# opencmxx.net
KiCad netlist of a schematic drawn in EAGLE
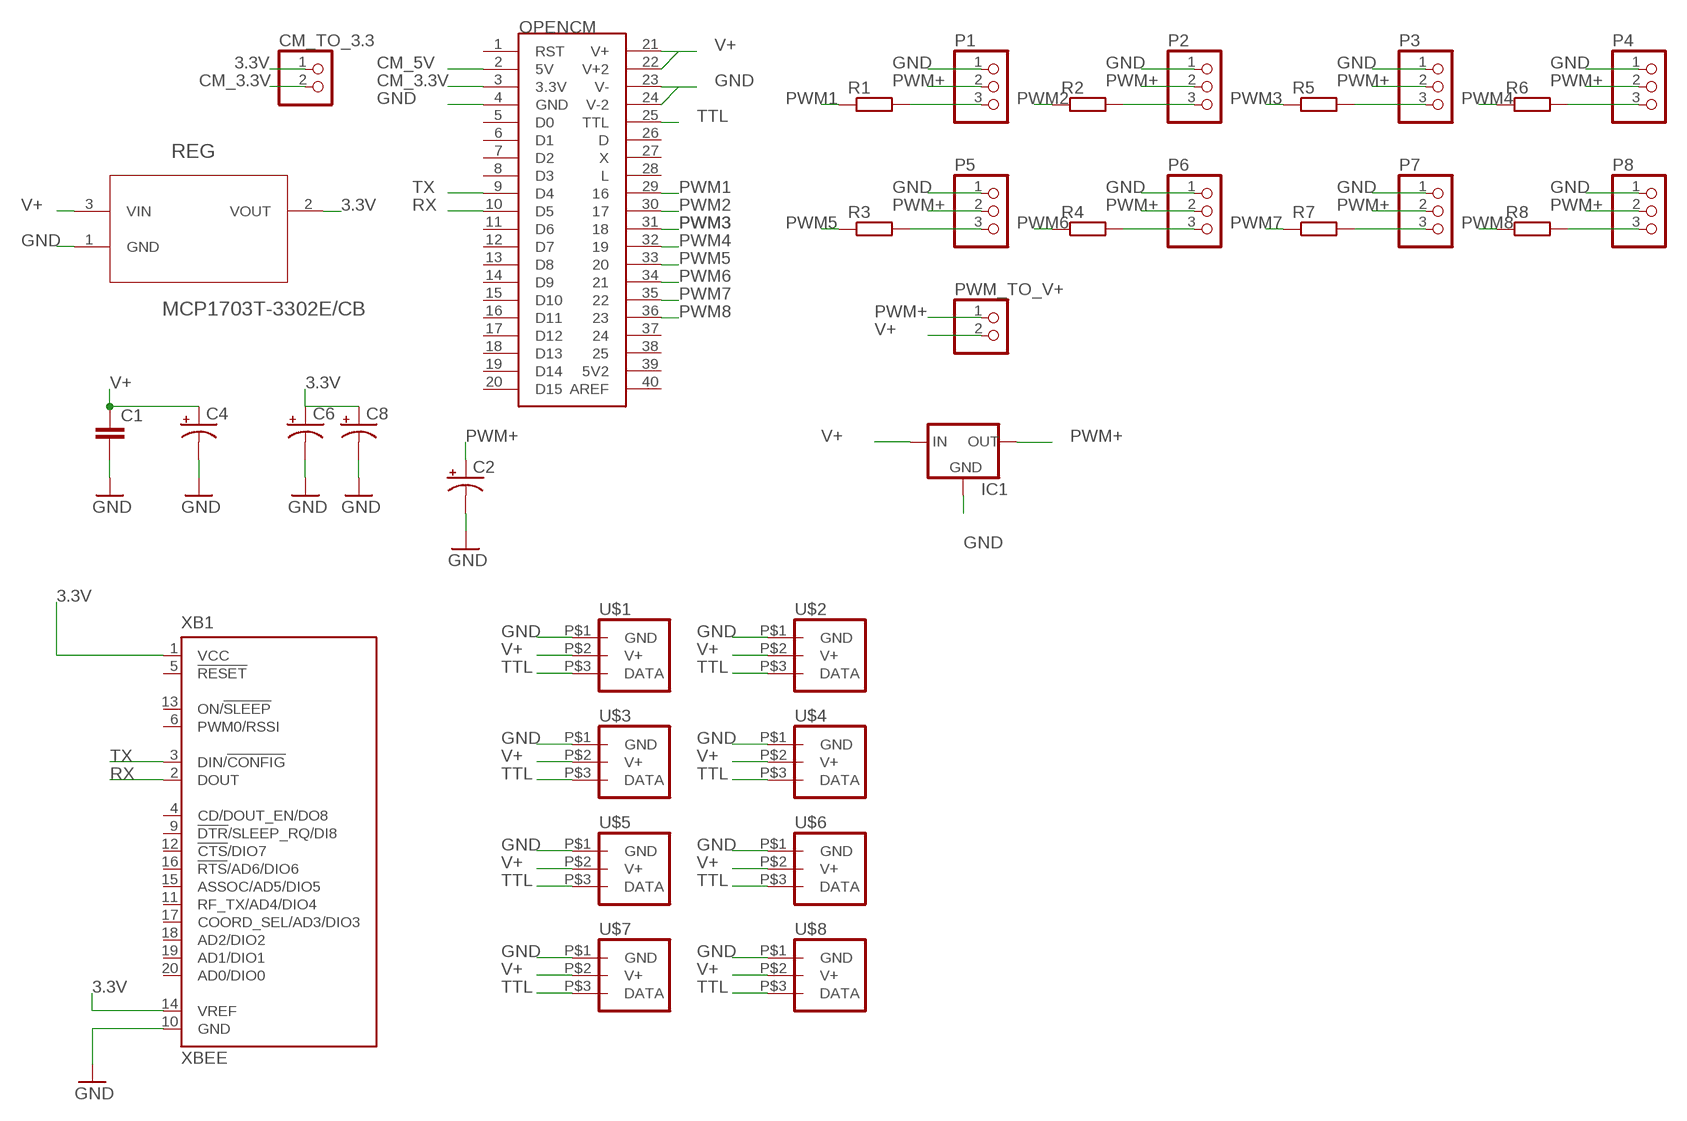
[diagram p0: schematic, sheet 1]

(export (version "E")
  (design (tool "Eeschema 10.0.6"))
  (components
    (comp (ref "C1")
      (value "C-EU075-032X103")
      (footprint "eagle-import:C075-032X103")
      (libsource (lib "eagle-import") (part "C-EU075-032X103"))
    )
    (comp (ref "C2")
      (value "CAP_POLPTH2")
      (footprint "eagle-import:CPOL-RADIAL-10UF-25V")
      (libsource (lib "eagle-import") (part "CAP_POLPTH2"))
    )
    (comp (ref "C4")
      (value "CAP_POLPTH2")
      (footprint "eagle-import:CPOL-RADIAL-10UF-25V")
      (libsource (lib "eagle-import") (part "CAP_POLPTH2"))
    )
    (comp (ref "C6")
      (value "CAP_POLPTH2")
      (footprint "eagle-import:CPOL-RADIAL-10UF-25V")
      (libsource (lib "eagle-import") (part "CAP_POLPTH2"))
    )
    (comp (ref "C8")
      (value "CAP_POLPTH2")
      (footprint "eagle-import:CPOL-RADIAL-10UF-25V")
      (libsource (lib "eagle-import") (part "CAP_POLPTH2"))
    )
    (comp (ref "CM_TO_3.3")
      (value "CONNEC_1X02")
      (footprint "eagle-import:CONNEC_1X02")
      (libsource (lib "eagle-import") (part "CONNEC_1X02"))
    )
    (comp (ref "IC1")
      (value "V_REG_78XXSIDE")
      (footprint "eagle-import:78XXL")
      (libsource (lib "eagle-import") (part "V_REG_78XXSIDE"))
    )
    (comp (ref "OPENCM")
      (value "OPENCM")
      (footprint "eagle-import:OPENCM")
      (libsource (lib "eagle-import") (part "OPENCM"))
    )
    (comp (ref "P1")
      (value "CONNEC_1X03")
      (footprint "eagle-import:CONNEC_1X03")
      (libsource (lib "eagle-import") (part "CONNEC_1X03"))
    )
    (comp (ref "P2")
      (value "CONNEC_1X03")
      (footprint "eagle-import:CONNEC_1X03")
      (libsource (lib "eagle-import") (part "CONNEC_1X03"))
    )
    (comp (ref "P3")
      (value "CONNEC_1X03")
      (footprint "eagle-import:CONNEC_1X03")
      (libsource (lib "eagle-import") (part "CONNEC_1X03"))
    )
    (comp (ref "P4")
      (value "CONNEC_1X03")
      (footprint "eagle-import:CONNEC_1X03")
      (libsource (lib "eagle-import") (part "CONNEC_1X03"))
    )
    (comp (ref "P5")
      (value "CONNEC_1X03")
      (footprint "eagle-import:CONNEC_1X03")
      (libsource (lib "eagle-import") (part "CONNEC_1X03"))
    )
    (comp (ref "P6")
      (value "CONNEC_1X03")
      (footprint "eagle-import:CONNEC_1X03")
      (libsource (lib "eagle-import") (part "CONNEC_1X03"))
    )
    (comp (ref "P7")
      (value "CONNEC_1X03")
      (footprint "eagle-import:CONNEC_1X03")
      (libsource (lib "eagle-import") (part "CONNEC_1X03"))
    )
    (comp (ref "P8")
      (value "CONNEC_1X03")
      (footprint "eagle-import:CONNEC_1X03")
      (libsource (lib "eagle-import") (part "CONNEC_1X03"))
    )
    (comp (ref "PWM_TO_V+")
      (value "CONNEC_1X02")
      (footprint "eagle-import:CONNEC_1X02")
      (libsource (lib "eagle-import") (part "CONNEC_1X02"))
    )
    (comp (ref "R1")
      (value "RESISTANCE-R0805")
      (footprint "eagle-import:R0805")
      (libsource (lib "eagle-import") (part "RESISTANCE-R0805"))
    )
    (comp (ref "R2")
      (value "RESISTANCE-R0805")
      (footprint "eagle-import:R0805")
      (libsource (lib "eagle-import") (part "RESISTANCE-R0805"))
    )
    (comp (ref "R3")
      (value "RESISTANCE-R0805")
      (footprint "eagle-import:R0805")
      (libsource (lib "eagle-import") (part "RESISTANCE-R0805"))
    )
    (comp (ref "R4")
      (value "RESISTANCE-R0805")
      (footprint "eagle-import:R0805")
      (libsource (lib "eagle-import") (part "RESISTANCE-R0805"))
    )
    (comp (ref "R5")
      (value "RESISTANCE-R0805")
      (footprint "eagle-import:R0805")
      (libsource (lib "eagle-import") (part "RESISTANCE-R0805"))
    )
    (comp (ref "R6")
      (value "RESISTANCE-R0805")
      (footprint "eagle-import:R0805")
      (libsource (lib "eagle-import") (part "RESISTANCE-R0805"))
    )
    (comp (ref "R7")
      (value "RESISTANCE-R0805")
      (footprint "eagle-import:R0805")
      (libsource (lib "eagle-import") (part "RESISTANCE-R0805"))
    )
    (comp (ref "R8")
      (value "RESISTANCE-R0805")
      (footprint "eagle-import:R0805")
      (libsource (lib "eagle-import") (part "RESISTANCE-R0805"))
    )
    (comp (ref "REG")
      (value "MCP1703T-3302E/CB")
      (footprint "eagle-import:SOT95P300X145-3N")
      (libsource (lib "eagle-import") (part "MCP1703T-3302E/CB"))
    )
    (comp (ref "U$1")
      (value "XL_320_CONNEC")
      (footprint "eagle-import:DXL_320_CONNEC")
      (libsource (lib "eagle-import") (part "XL_320_CONNEC"))
    )
    (comp (ref "U$2")
      (value "XL_320_CONNEC")
      (footprint "eagle-import:DXL_320_CONNEC")
      (libsource (lib "eagle-import") (part "XL_320_CONNEC"))
    )
    (comp (ref "U$3")
      (value "XL_320_CONNEC")
      (footprint "eagle-import:DXL_320_CONNEC")
      (libsource (lib "eagle-import") (part "XL_320_CONNEC"))
    )
    (comp (ref "U$4")
      (value "XL_320_CONNEC")
      (footprint "eagle-import:DXL_320_CONNEC")
      (libsource (lib "eagle-import") (part "XL_320_CONNEC"))
    )
    (comp (ref "U$5")
      (value "XL_320_CONNEC")
      (footprint "eagle-import:DXL_320_CONNEC")
      (libsource (lib "eagle-import") (part "XL_320_CONNEC"))
    )
    (comp (ref "U$6")
      (value "XL_320_CONNEC")
      (footprint "eagle-import:DXL_320_CONNEC")
      (libsource (lib "eagle-import") (part "XL_320_CONNEC"))
    )
    (comp (ref "U$7")
      (value "XL_320_CONNEC")
      (footprint "eagle-import:DXL_320_CONNEC")
      (libsource (lib "eagle-import") (part "XL_320_CONNEC"))
    )
    (comp (ref "U$8")
      (value "XL_320_CONNEC")
      (footprint "eagle-import:DXL_320_CONNEC")
      (libsource (lib "eagle-import") (part "XL_320_CONNEC"))
    )
    (comp (ref "XB1")
      (value "XBEE")
      (footprint "eagle-import:XBEE")
      (fields (field (name "MPN") "XBP24-Z7UIT-004"))
      (libsource (lib "eagle-import") (part "XBEE"))
    )
  )
  (nets
    (net (code "1") (name "/3.3V") (class "Default")
      (node (ref "C6") (pin "1") (pinfunction "+_1") (pintype "passive"))
      (node (ref "C8") (pin "1") (pinfunction "+_1") (pintype "passive"))
      (node (ref "CM_TO_3.3") (pin "1") (pinfunction "1_1") (pintype "passive"))
      (node (ref "REG") (pin "2") (pinfunction "VOUT_2") (pintype "output"))
      (node (ref "XB1") (pin "1") (pinfunction "VCC_1") (pintype "power_in"))
      (node (ref "XB1") (pin "14") (pinfunction "VREF_14") (pintype "input"))
    )
    (net (code "2") (name "/CM_3.3V") (class "Default")
      (node (ref "CM_TO_3.3") (pin "2") (pinfunction "2_2") (pintype "passive"))
      (node (ref "OPENCM") (pin "3") (pinfunction "3.3V_3") (pintype "bidirectional"))
    )
    (net (code "3") (name "/CM_5V") (class "Default")
      (node (ref "OPENCM") (pin "2") (pinfunction "5V_2") (pintype "bidirectional"))
    )
    (net (code "4") (name "/PWM+") (class "Default")
      (node (ref "C2") (pin "1") (pinfunction "+_1") (pintype "passive"))
      (node (ref "IC1") (pin "OUT") (pinfunction "OUT_OUT") (pintype "output"))
      (node (ref "P1") (pin "2") (pinfunction "2_2") (pintype "passive"))
      (node (ref "P2") (pin "2") (pinfunction "2_2") (pintype "passive"))
      (node (ref "P3") (pin "2") (pinfunction "2_2") (pintype "passive"))
      (node (ref "P4") (pin "2") (pinfunction "2_2") (pintype "passive"))
      (node (ref "P5") (pin "2") (pinfunction "2_2") (pintype "passive"))
      (node (ref "P6") (pin "2") (pinfunction "2_2") (pintype "passive"))
      (node (ref "P7") (pin "2") (pinfunction "2_2") (pintype "passive"))
      (node (ref "P8") (pin "2") (pinfunction "2_2") (pintype "passive"))
      (node (ref "PWM_TO_V+") (pin "1") (pinfunction "1_1") (pintype "passive"))
    )
    (net (code "5") (name "/PWM1") (class "Default")
      (node (ref "OPENCM") (pin "29") (pinfunction "16_29") (pintype "bidirectional"))
      (node (ref "R1") (pin "1") (pinfunction "1_1") (pintype "passive"))
    )
    (net (code "6") (name "/PWM2") (class "Default")
      (node (ref "OPENCM") (pin "30") (pinfunction "17_30") (pintype "bidirectional"))
      (node (ref "R2") (pin "1") (pinfunction "1_1") (pintype "passive"))
    )
    (net (code "7") (name "/PWM3") (class "Default")
      (node (ref "OPENCM") (pin "31") (pinfunction "18_31") (pintype "bidirectional"))
      (node (ref "R5") (pin "1") (pinfunction "1_1") (pintype "passive"))
    )
    (net (code "8") (name "/PWM4") (class "Default")
      (node (ref "OPENCM") (pin "32") (pinfunction "19_32") (pintype "bidirectional"))
      (node (ref "R6") (pin "1") (pinfunction "1_1") (pintype "passive"))
    )
    (net (code "9") (name "/PWM5") (class "Default")
      (node (ref "OPENCM") (pin "33") (pinfunction "20_33") (pintype "bidirectional"))
      (node (ref "R3") (pin "1") (pinfunction "1_1") (pintype "passive"))
    )
    (net (code "10") (name "/PWM6") (class "Default")
      (node (ref "OPENCM") (pin "34") (pinfunction "21_34") (pintype "bidirectional"))
      (node (ref "R4") (pin "1") (pinfunction "1_1") (pintype "passive"))
    )
    (net (code "11") (name "/PWM7") (class "Default")
      (node (ref "OPENCM") (pin "35") (pinfunction "22_35") (pintype "bidirectional"))
      (node (ref "R7") (pin "1") (pinfunction "1_1") (pintype "passive"))
    )
    (net (code "12") (name "/PWM8") (class "Default")
      (node (ref "OPENCM") (pin "36") (pinfunction "23_36") (pintype "bidirectional"))
      (node (ref "R8") (pin "1") (pinfunction "1_1") (pintype "passive"))
    )
    (net (code "13") (name "/RX") (class "Default")
      (node (ref "OPENCM") (pin "10") (pinfunction "D5_10") (pintype "bidirectional"))
      (node (ref "XB1") (pin "2") (pinfunction "DOUT_2") (pintype "output"))
    )
    (net (code "14") (name "/TTL") (class "Default")
      (node (ref "OPENCM") (pin "25") (pinfunction "TTL_25") (pintype "bidirectional"))
      (node (ref "U$1") (pin "P$3") (pinfunction "DATA_P$3") (pintype "bidirectional"))
      (node (ref "U$2") (pin "P$3") (pinfunction "DATA_P$3") (pintype "bidirectional"))
      (node (ref "U$3") (pin "P$3") (pinfunction "DATA_P$3") (pintype "bidirectional"))
      (node (ref "U$4") (pin "P$3") (pinfunction "DATA_P$3") (pintype "bidirectional"))
      (node (ref "U$5") (pin "P$3") (pinfunction "DATA_P$3") (pintype "bidirectional"))
      (node (ref "U$6") (pin "P$3") (pinfunction "DATA_P$3") (pintype "bidirectional"))
      (node (ref "U$7") (pin "P$3") (pinfunction "DATA_P$3") (pintype "bidirectional"))
      (node (ref "U$8") (pin "P$3") (pinfunction "DATA_P$3") (pintype "bidirectional"))
    )
    (net (code "15") (name "/TX") (class "Default")
      (node (ref "OPENCM") (pin "9") (pinfunction "D4_9") (pintype "bidirectional"))
      (node (ref "XB1") (pin "3") (pinfunction "DIN/~{CONFIG}_3") (pintype "input"))
    )
    (net (code "16") (name "/V+") (class "Default")
      (node (ref "C1") (pin "1") (pinfunction "1_1") (pintype "passive"))
      (node (ref "C4") (pin "1") (pinfunction "+_1") (pintype "passive"))
      (node (ref "IC1") (pin "IN") (pinfunction "IN_IN") (pintype "input"))
      (node (ref "OPENCM") (pin "21") (pinfunction "V+_21") (pintype "bidirectional"))
      (node (ref "OPENCM") (pin "22") (pinfunction "V+2_22") (pintype "bidirectional"))
      (node (ref "PWM_TO_V+") (pin "2") (pinfunction "2_2") (pintype "passive"))
      (node (ref "REG") (pin "3") (pinfunction "VIN_3") (pintype "input"))
      (node (ref "U$1") (pin "P$2") (pinfunction "V+_P$2") (pintype "bidirectional"))
      (node (ref "U$2") (pin "P$2") (pinfunction "V+_P$2") (pintype "bidirectional"))
      (node (ref "U$3") (pin "P$2") (pinfunction "V+_P$2") (pintype "bidirectional"))
      (node (ref "U$4") (pin "P$2") (pinfunction "V+_P$2") (pintype "bidirectional"))
      (node (ref "U$5") (pin "P$2") (pinfunction "V+_P$2") (pintype "bidirectional"))
      (node (ref "U$6") (pin "P$2") (pinfunction "V+_P$2") (pintype "bidirectional"))
      (node (ref "U$7") (pin "P$2") (pinfunction "V+_P$2") (pintype "bidirectional"))
      (node (ref "U$8") (pin "P$2") (pinfunction "V+_P$2") (pintype "bidirectional"))
    )
    (net (code "17") (name "GND") (class "Default")
      (node (ref "C1") (pin "2") (pinfunction "2_2") (pintype "passive"))
      (node (ref "C2") (pin "2") (pinfunction "-_2") (pintype "passive"))
      (node (ref "C4") (pin "2") (pinfunction "-_2") (pintype "passive"))
      (node (ref "C6") (pin "2") (pinfunction "-_2") (pintype "passive"))
      (node (ref "C8") (pin "2") (pinfunction "-_2") (pintype "passive"))
      (node (ref "IC1") (pin "GND") (pinfunction "GND_GND") (pintype "input"))
      (node (ref "OPENCM") (pin "23") (pinfunction "V-_23") (pintype "bidirectional"))
      (node (ref "OPENCM") (pin "24") (pinfunction "V-2_24") (pintype "bidirectional"))
      (node (ref "OPENCM") (pin "4") (pinfunction "GND_4") (pintype "bidirectional"))
      (node (ref "P1") (pin "1") (pinfunction "1_1") (pintype "passive"))
      (node (ref "P2") (pin "1") (pinfunction "1_1") (pintype "passive"))
      (node (ref "P3") (pin "1") (pinfunction "1_1") (pintype "passive"))
      (node (ref "P4") (pin "1") (pinfunction "1_1") (pintype "passive"))
      (node (ref "P5") (pin "1") (pinfunction "1_1") (pintype "passive"))
      (node (ref "P6") (pin "1") (pinfunction "1_1") (pintype "passive"))
      (node (ref "P7") (pin "1") (pinfunction "1_1") (pintype "passive"))
      (node (ref "P8") (pin "1") (pinfunction "1_1") (pintype "passive"))
      (node (ref "REG") (pin "1") (pinfunction "GND_1") (pintype "passive"))
      (node (ref "U$1") (pin "P$1") (pinfunction "GND_P$1") (pintype "bidirectional"))
      (node (ref "U$2") (pin "P$1") (pinfunction "GND_P$1") (pintype "bidirectional"))
      (node (ref "U$3") (pin "P$1") (pinfunction "GND_P$1") (pintype "bidirectional"))
      (node (ref "U$4") (pin "P$1") (pinfunction "GND_P$1") (pintype "bidirectional"))
      (node (ref "U$5") (pin "P$1") (pinfunction "GND_P$1") (pintype "bidirectional"))
      (node (ref "U$6") (pin "P$1") (pinfunction "GND_P$1") (pintype "bidirectional"))
      (node (ref "U$7") (pin "P$1") (pinfunction "GND_P$1") (pintype "bidirectional"))
      (node (ref "U$8") (pin "P$1") (pinfunction "GND_P$1") (pintype "bidirectional"))
      (node (ref "XB1") (pin "10") (pinfunction "GND_10") (pintype "power_in"))
    )
    (net (code "18") (name "Net-(P1-Pad3)") (class "Default")
      (node (ref "P1") (pin "3") (pinfunction "3_3") (pintype "passive"))
      (node (ref "R1") (pin "2") (pinfunction "2_2") (pintype "passive"))
    )
    (net (code "19") (name "Net-(P2-Pad3)") (class "Default")
      (node (ref "P2") (pin "3") (pinfunction "3_3") (pintype "passive"))
      (node (ref "R2") (pin "2") (pinfunction "2_2") (pintype "passive"))
    )
    (net (code "20") (name "Net-(P3-Pad3)") (class "Default")
      (node (ref "P3") (pin "3") (pinfunction "3_3") (pintype "passive"))
      (node (ref "R5") (pin "2") (pinfunction "2_2") (pintype "passive"))
    )
    (net (code "21") (name "Net-(P4-Pad3)") (class "Default")
      (node (ref "P4") (pin "3") (pinfunction "3_3") (pintype "passive"))
      (node (ref "R6") (pin "2") (pinfunction "2_2") (pintype "passive"))
    )
    (net (code "22") (name "Net-(P5-Pad3)") (class "Default")
      (node (ref "P5") (pin "3") (pinfunction "3_3") (pintype "passive"))
      (node (ref "R3") (pin "2") (pinfunction "2_2") (pintype "passive"))
    )
    (net (code "23") (name "Net-(P6-Pad3)") (class "Default")
      (node (ref "P6") (pin "3") (pinfunction "3_3") (pintype "passive"))
      (node (ref "R4") (pin "2") (pinfunction "2_2") (pintype "passive"))
    )
    (net (code "24") (name "Net-(P7-Pad3)") (class "Default")
      (node (ref "P7") (pin "3") (pinfunction "3_3") (pintype "passive"))
      (node (ref "R7") (pin "2") (pinfunction "2_2") (pintype "passive"))
    )
    (net (code "25") (name "Net-(P8-Pad3)") (class "Default")
      (node (ref "P8") (pin "3") (pinfunction "3_3") (pintype "passive"))
      (node (ref "R8") (pin "2") (pinfunction "2_2") (pintype "passive"))
    )
    (net (code "26") (name "unconnected-(OPENCM-5V2-Pad39)") (class "Default")
      (node (ref "OPENCM") (pin "39") (pinfunction "5V2_39") (pintype "bidirectional"))
    )
    (net (code "27") (name "unconnected-(OPENCM-24-Pad37)") (class "Default")
      (node (ref "OPENCM") (pin "37") (pinfunction "24_37") (pintype "bidirectional"))
    )
    (net (code "28") (name "unconnected-(OPENCM-25-Pad38)") (class "Default")
      (node (ref "OPENCM") (pin "38") (pinfunction "25_38") (pintype "bidirectional"))
    )
    (net (code "29") (name "unconnected-(OPENCM-AREF-Pad40)") (class "Default")
      (node (ref "OPENCM") (pin "40") (pinfunction "AREF_40") (pintype "bidirectional"))
    )
    (net (code "30") (name "unconnected-(OPENCM-D-Pad26)") (class "Default")
      (node (ref "OPENCM") (pin "26") (pinfunction "D_26") (pintype "bidirectional"))
    )
    (net (code "31") (name "unconnected-(OPENCM-D0-Pad5)") (class "Default")
      (node (ref "OPENCM") (pin "5") (pinfunction "D0_5") (pintype "bidirectional"))
    )
    (net (code "32") (name "unconnected-(OPENCM-D1-Pad6)") (class "Default")
      (node (ref "OPENCM") (pin "6") (pinfunction "D1_6") (pintype "bidirectional"))
    )
    (net (code "33") (name "unconnected-(OPENCM-D2-Pad7)") (class "Default")
      (node (ref "OPENCM") (pin "7") (pinfunction "D2_7") (pintype "bidirectional"))
    )
    (net (code "34") (name "unconnected-(OPENCM-D3-Pad8)") (class "Default")
      (node (ref "OPENCM") (pin "8") (pinfunction "D3_8") (pintype "bidirectional"))
    )
    (net (code "35") (name "unconnected-(OPENCM-D6-Pad11)") (class "Default")
      (node (ref "OPENCM") (pin "11") (pinfunction "D6_11") (pintype "bidirectional"))
    )
    (net (code "36") (name "unconnected-(OPENCM-D7-Pad12)") (class "Default")
      (node (ref "OPENCM") (pin "12") (pinfunction "D7_12") (pintype "bidirectional"))
    )
    (net (code "37") (name "unconnected-(OPENCM-D8-Pad13)") (class "Default")
      (node (ref "OPENCM") (pin "13") (pinfunction "D8_13") (pintype "bidirectional"))
    )
    (net (code "38") (name "unconnected-(OPENCM-D9-Pad14)") (class "Default")
      (node (ref "OPENCM") (pin "14") (pinfunction "D9_14") (pintype "bidirectional"))
    )
    (net (code "39") (name "unconnected-(OPENCM-D10-Pad15)") (class "Default")
      (node (ref "OPENCM") (pin "15") (pinfunction "D10_15") (pintype "bidirectional"))
    )
    (net (code "40") (name "unconnected-(OPENCM-D11-Pad16)") (class "Default")
      (node (ref "OPENCM") (pin "16") (pinfunction "D11_16") (pintype "bidirectional"))
    )
    (net (code "41") (name "unconnected-(OPENCM-D12-Pad17)") (class "Default")
      (node (ref "OPENCM") (pin "17") (pinfunction "D12_17") (pintype "bidirectional"))
    )
    (net (code "42") (name "unconnected-(OPENCM-D13-Pad18)") (class "Default")
      (node (ref "OPENCM") (pin "18") (pinfunction "D13_18") (pintype "bidirectional"))
    )
    (net (code "43") (name "unconnected-(OPENCM-D14-Pad19)") (class "Default")
      (node (ref "OPENCM") (pin "19") (pinfunction "D14_19") (pintype "bidirectional"))
    )
    (net (code "44") (name "unconnected-(OPENCM-D15-Pad20)") (class "Default")
      (node (ref "OPENCM") (pin "20") (pinfunction "D15_20") (pintype "bidirectional"))
    )
    (net (code "45") (name "unconnected-(OPENCM-L-Pad28)") (class "Default")
      (node (ref "OPENCM") (pin "28") (pinfunction "L_28") (pintype "bidirectional"))
    )
    (net (code "46") (name "unconnected-(OPENCM-RST-Pad1)") (class "Default")
      (node (ref "OPENCM") (pin "1") (pinfunction "RST_1") (pintype "bidirectional"))
    )
    (net (code "47") (name "unconnected-(OPENCM-X-Pad27)") (class "Default")
      (node (ref "OPENCM") (pin "27") (pinfunction "X_27") (pintype "bidirectional"))
    )
    (net (code "48") (name "unconnected-(XB1-AD0{slash}DIO0-Pad20)") (class "Default")
      (node (ref "XB1") (pin "20") (pinfunction "AD0/DIO0_20") (pintype "bidirectional"))
    )
    (net (code "49") (name "unconnected-(XB1-AD1{slash}DIO1-Pad19)") (class "Default")
      (node (ref "XB1") (pin "19") (pinfunction "AD1/DIO1_19") (pintype "bidirectional"))
    )
    (net (code "50") (name "unconnected-(XB1-AD2{slash}DIO2-Pad18)") (class "Default")
      (node (ref "XB1") (pin "18") (pinfunction "AD2/DIO2_18") (pintype "bidirectional"))
    )
    (net (code "51") (name "unconnected-(XB1-ASSOC{slash}AD5{slash}DIO5-Pad15)") (class "Default")
      (node (ref "XB1") (pin "15") (pinfunction "ASSOC/AD5/DIO5_15") (pintype "bidirectional"))
    )
    (net (code "52") (name "unconnected-(XB1-CD{slash}DOUT_EN{slash}DO8-Pad4)") (class "Default")
      (node (ref "XB1") (pin "4") (pinfunction "CD/DOUT_EN/DO8_4") (pintype "output"))
    )
    (net (code "53") (name "unconnected-(XB1-COORD_SEL{slash}AD3{slash}DIO3-Pad17)") (class "Default")
      (node (ref "XB1") (pin "17") (pinfunction "COORD_SEL/AD3/DIO3_17") (pintype "bidirectional"))
    )
    (net (code "54") (name "unconnected-(XB1-ON{slash}~{SLEEP}-Pad13)") (class "Default")
      (node (ref "XB1") (pin "13") (pinfunction "ON/~{SLEEP}_13") (pintype "output"))
    )
    (net (code "55") (name "unconnected-(XB1-PWM0{slash}RSSI-Pad6)") (class "Default")
      (node (ref "XB1") (pin "6") (pinfunction "PWM0/RSSI_6") (pintype "output"))
    )
    (net (code "56") (name "unconnected-(XB1-RF_TX{slash}AD4{slash}DIO4-Pad11)") (class "Default")
      (node (ref "XB1") (pin "11") (pinfunction "RF_TX/AD4/DIO4_11") (pintype "bidirectional"))
    )
    (net (code "57") (name "unconnected-(XB1-~{CTS}{slash}DIO7-Pad12)") (class "Default")
      (node (ref "XB1") (pin "12") (pinfunction "~{CTS}/DIO7_12") (pintype "bidirectional"))
    )
    (net (code "58") (name "unconnected-(XB1-~{DTR}{slash}SLEEP_RQ{slash}DI8-Pad9)") (class "Default")
      (node (ref "XB1") (pin "9") (pinfunction "~{DTR}/SLEEP_RQ/DI8_9") (pintype "bidirectional"))
    )
    (net (code "59") (name "unconnected-(XB1-~{RESET}-Pad5)") (class "Default")
      (node (ref "XB1") (pin "5") (pinfunction "~{RESET}_5") (pintype "input"))
    )
    (net (code "60") (name "unconnected-(XB1-~{RTS}{slash}AD6{slash}DIO6-Pad16)") (class "Default")
      (node (ref "XB1") (pin "16") (pinfunction "~{RTS}/AD6/DIO6_16") (pintype "bidirectional"))
    )
  )
)
